# magspoof.net
KiCad netlist of a schematic drawn in EAGLE
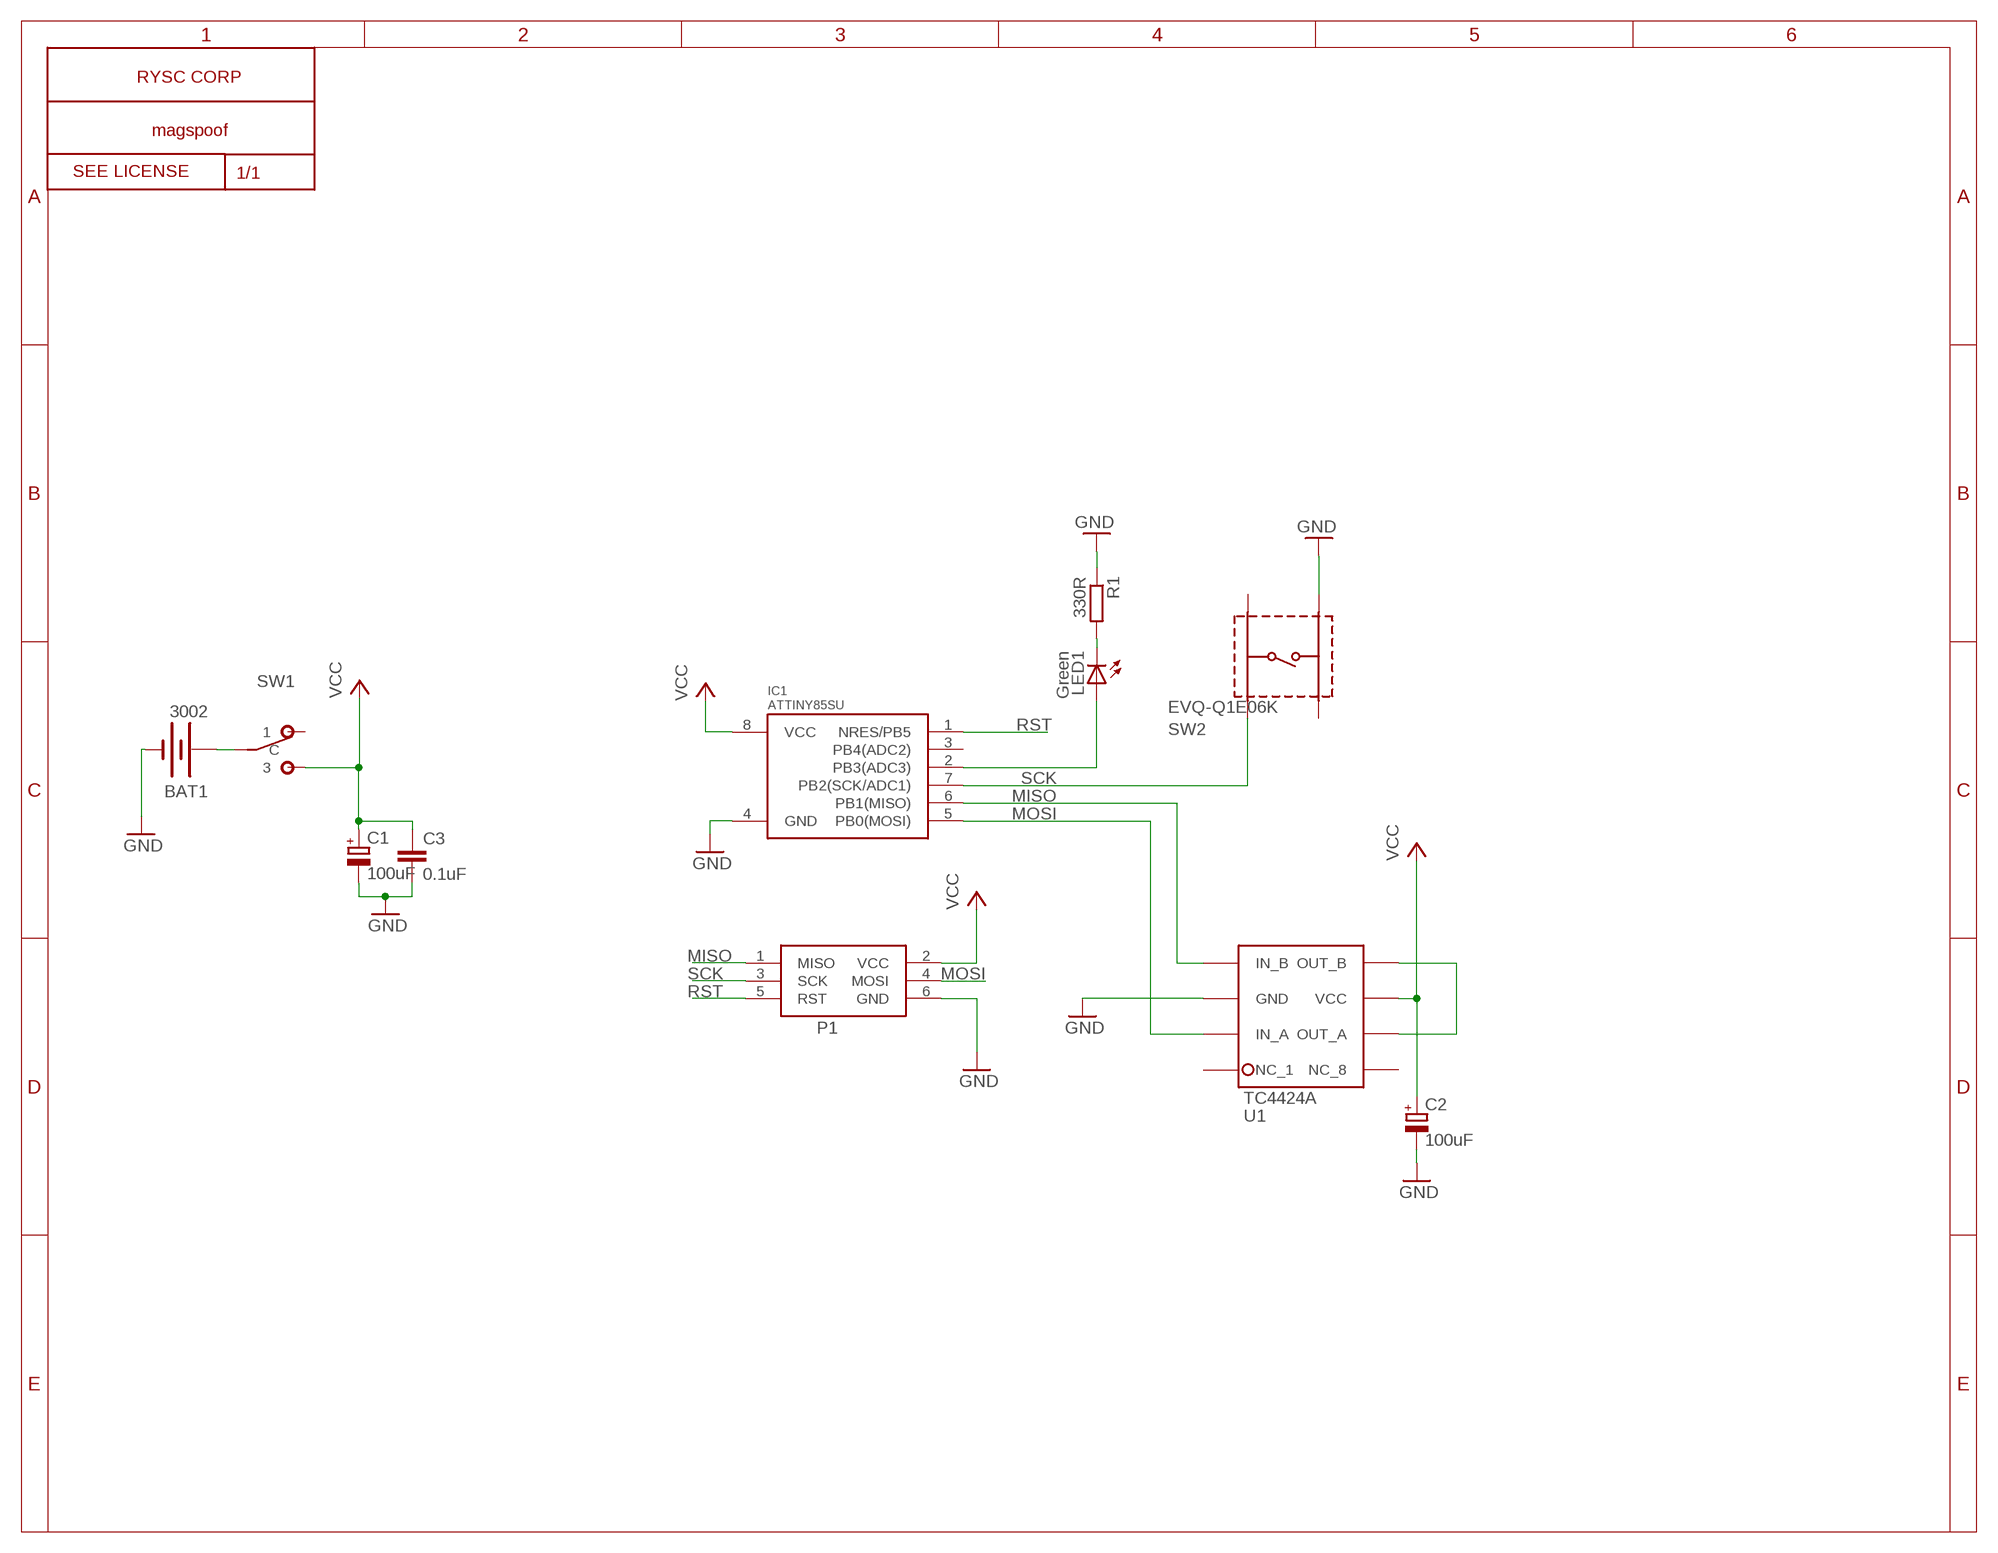
[diagram p0: schematic, sheet 1]

(export (version "E")
  (design (tool "Eeschema 10.0.6"))
  (components
    (comp (ref "BAT1")
      (value "3002")
      (footprint "eagle-import:BATTCON_20MM")
      (libsource (lib "eagle-import") (part "3002"))
    )
    (comp (ref "C1")
      (value "100uF")
      (footprint "eagle-import:C1411")
      (libsource (lib "eagle-import") (part "CPOL-EU"))
    )
    (comp (ref "C2")
      (value "100uF")
      (footprint "eagle-import:C1411")
      (libsource (lib "eagle-import") (part "CPOL-EU"))
    )
    (comp (ref "C3")
      (value "0.1uF")
      (footprint "eagle-import:C0603")
      (libsource (lib "eagle-import") (part "C-EUC0603"))
    )
    (comp (ref "IC1")
      (value "ATTINY85SU")
      (footprint "eagle-import:ATTINY85")
      (libsource (lib "eagle-import") (part "ATTINY85SU"))
    )
    (comp (ref "LED1")
      (value "Green")
      (footprint "eagle-import:CHIPLED_0805")
      (libsource (lib "eagle-import") (part "LEDCHIPLED_0805"))
    )
    (comp (ref "P1")
      (value "AVRISP-6")
      (footprint "eagle-import:AVRISP")
      (libsource (lib "eagle-import") (part "AVRISP-6"))
    )
    (comp (ref "R1")
      (value "330R")
      (footprint "eagle-import:R0603")
      (libsource (lib "eagle-import") (part "R-EU_R0603"))
    )
    (comp (ref "SW1")
      (value "JS102011")
      (footprint "eagle-import:JS102011SAQN")
      (libsource (lib "eagle-import") (part "JS102011"))
    )
    (comp (ref "SW2")
      (value "EVQ-Q1E06K")
      (footprint "eagle-import:EVQQ1")
      (libsource (lib "eagle-import") (part "EVQQ1"))
    )
    (comp (ref "U1")
      (value "TC4424A")
      (footprint "eagle-import:8-SOIC")
      (libsource (lib "eagle-import") (part "TC4424A"))
    )
  )
  (nets
    (net (code "1") (name "/MISO") (class "Default")
      (node (ref "IC1") (pin "6") (pinfunction "PB1(MISO)_6") (pintype "bidirectional"))
      (node (ref "P1") (pin "1") (pinfunction "MISO_1") (pintype "input"))
      (node (ref "U1") (pin "4") (pinfunction "IN_B_4") (pintype "bidirectional"))
    )
    (net (code "2") (name "/MOSI") (class "Default")
      (node (ref "IC1") (pin "5") (pinfunction "PB0(MOSI)_5") (pintype "bidirectional"))
      (node (ref "P1") (pin "4") (pinfunction "MOSI_4") (pintype "output"))
      (node (ref "U1") (pin "2") (pinfunction "IN_A_2") (pintype "bidirectional"))
    )
    (net (code "3") (name "/RST") (class "Default")
      (node (ref "IC1") (pin "1") (pinfunction "NRES/PB5_1") (pintype "bidirectional"))
      (node (ref "P1") (pin "5") (pinfunction "RST_5") (pintype "output"))
    )
    (net (code "4") (name "/SCK") (class "Default")
      (node (ref "IC1") (pin "7") (pinfunction "PB2(SCK/ADC1)_7") (pintype "bidirectional"))
      (node (ref "P1") (pin "3") (pinfunction "SCK_3") (pintype "output"))
      (node (ref "SW2") (pin "A") (pinfunction "P$1_A") (pintype "bidirectional"))
    )
    (net (code "5") (name "GND") (class "Default")
      (node (ref "BAT1") (pin "-") (pinfunction "-_-") (pintype "power_in"))
      (node (ref "C1") (pin "P$2") (pinfunction "-_P$2") (pintype "passive"))
      (node (ref "C2") (pin "P$2") (pinfunction "-_P$2") (pintype "passive"))
      (node (ref "C3") (pin "2") (pinfunction "2_2") (pintype "passive"))
      (node (ref "IC1") (pin "4") (pinfunction "GND_4") (pintype "power_in"))
      (node (ref "P1") (pin "6") (pinfunction "GND_6") (pintype "power_in"))
      (node (ref "R1") (pin "1") (pinfunction "1_1") (pintype "passive"))
      (node (ref "SW2") (pin "D") (pinfunction "P$4_D") (pintype "bidirectional"))
      (node (ref "U1") (pin "3") (pinfunction "GND_3") (pintype "power_in"))
    )
    (net (code "6") (name "Net-(BAT1-+)") (class "Default")
      (node (ref "BAT1") (pin "+2") (pinfunction "+_+2") (pintype "power_in"))
      (node (ref "SW1") (pin "P$2") (pinfunction "C_P$2") (pintype "passive"))
    )
    (net (code "7") (name "Net-(IC1-PB3(ADC3))") (class "Default")
      (node (ref "IC1") (pin "2") (pinfunction "PB3(ADC3)_2") (pintype "bidirectional"))
      (node (ref "LED1") (pin "A") (pinfunction "A_A") (pintype "passive"))
    )
    (net (code "8") (name "Net-(LED1-PadC)") (class "Default")
      (node (ref "LED1") (pin "C") (pinfunction "C_C") (pintype "passive"))
      (node (ref "R1") (pin "2") (pinfunction "2_2") (pintype "passive"))
    )
    (net (code "9") (name "Net-(U1-OUT_A)") (class "Default")
      (node (ref "U1") (pin "5") (pinfunction "OUT_B_5") (pintype "bidirectional"))
      (node (ref "U1") (pin "7") (pinfunction "OUT_A_7") (pintype "bidirectional"))
    )
    (net (code "10") (name "VCC") (class "Default")
      (node (ref "C1") (pin "P$1") (pinfunction "+_P$1") (pintype "passive"))
      (node (ref "C2") (pin "P$1") (pinfunction "+_P$1") (pintype "passive"))
      (node (ref "C3") (pin "1") (pinfunction "1_1") (pintype "passive"))
      (node (ref "IC1") (pin "8") (pinfunction "VCC_8") (pintype "power_in"))
      (node (ref "P1") (pin "2") (pinfunction "VCC_2") (pintype "power_in"))
      (node (ref "SW1") (pin "P$3") (pinfunction "3_P$3") (pintype "passive"))
      (node (ref "U1") (pin "6") (pinfunction "VCC_6") (pintype "power_in"))
    )
    (net (code "11") (name "unconnected-(IC1-PB4(ADC2)-Pad3)") (class "Default")
      (node (ref "IC1") (pin "3") (pinfunction "PB4(ADC2)_3") (pintype "bidirectional"))
    )
    (net (code "12") (name "unconnected-(SW1-1-PadP$1)") (class "Default")
      (node (ref "SW1") (pin "P$1") (pinfunction "1_P$1") (pintype "passive"))
    )
    (net (code "13") (name "unconnected-(SW2-P$2-PadB)") (class "Default")
      (node (ref "SW2") (pin "B") (pinfunction "P$2_B") (pintype "bidirectional"))
    )
    (net (code "14") (name "unconnected-(SW2-P$3-PadC)") (class "Default")
      (node (ref "SW2") (pin "C") (pinfunction "P$3_C") (pintype "bidirectional"))
    )
    (net (code "15") (name "unconnected-(U1-NC_1-Pad1)") (class "Default")
      (node (ref "U1") (pin "1") (pinfunction "NC_1_1") (pintype "no_connect"))
    )
    (net (code "16") (name "unconnected-(U1-NC_8-Pad8)") (class "Default")
      (node (ref "U1") (pin "8") (pinfunction "NC_8_8") (pintype "no_connect"))
    )
  )
)
